# untitled1.net
KiCad netlist of a schematic drawn in EAGLE
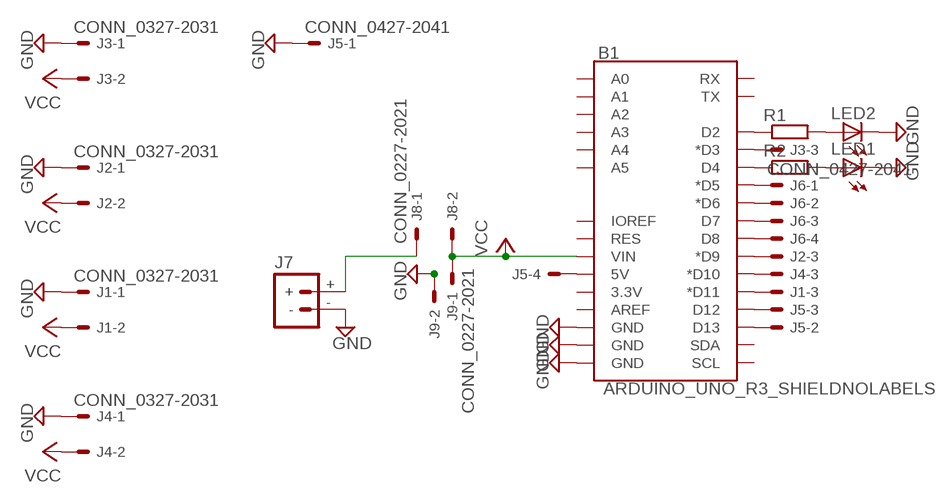
[diagram p0: schematic, sheet 1]

(export (version "E")
  (design (tool "Eeschema 10.0.6"))
  (components
    (comp (ref "B1")
      (value "ARDUINO_UNO_R3_SHIELDNOLABELS")
      (footprint "eagle-import:UNO_R3_SHIELD_NOLABELS")
      (libsource (lib "eagle-import") (part "ARDUINO_UNO_R3_SHIELDNOLABELS"))
    )
    (comp (ref "J1")
      (value "CONN_0327-2031")
      (footprint "eagle-import:6410-03")
      (libsource (lib "eagle-import") (part "CONN_0327-2031"))
    )
    (comp (ref "J2")
      (value "CONN_0327-2031")
      (footprint "eagle-import:6410-03")
      (libsource (lib "eagle-import") (part "CONN_0327-2031"))
    )
    (comp (ref "J3")
      (value "CONN_0327-2031")
      (footprint "eagle-import:6410-03")
      (libsource (lib "eagle-import") (part "CONN_0327-2031"))
    )
    (comp (ref "J4")
      (value "CONN_0327-2031")
      (footprint "eagle-import:6410-03")
      (libsource (lib "eagle-import") (part "CONN_0327-2031"))
    )
    (comp (ref "J5")
      (value "CONN_0427-2041")
      (footprint "eagle-import:6410-04")
      (libsource (lib "eagle-import") (part "CONN_0427-2041"))
    )
    (comp (ref "J6")
      (value "CONN_0427-2041")
      (footprint "eagle-import:6410-04")
      (libsource (lib "eagle-import") (part "CONN_0427-2041"))
    )
    (comp (ref "J7")
      (value "BATTERY_CONNXT60")
      (footprint "eagle-import:XT60")
      (libsource (lib "eagle-import") (part "BATTERY_CONNXT60"))
    )
    (comp (ref "J8")
      (value "CONN_0227-2021")
      (footprint "eagle-import:6410-02")
      (libsource (lib "eagle-import") (part "CONN_0227-2021"))
    )
    (comp (ref "J9")
      (value "CONN_0227-2021")
      (footprint "eagle-import:6410-02")
      (libsource (lib "eagle-import") (part "CONN_0227-2021"))
    )
    (comp (ref "LED1")
      (value "LED5MM")
      (footprint "eagle-import:LED5MM")
      (libsource (lib "eagle-import") (part "LED5MM"))
    )
    (comp (ref "LED2")
      (value "LED5MM")
      (footprint "eagle-import:LED5MM")
      (libsource (lib "eagle-import") (part "LED5MM"))
    )
    (comp (ref "R1")
      (value "R-EU_0204/7")
      (footprint "eagle-import:0204_7")
      (libsource (lib "eagle-import") (part "R-EU_0204/7"))
    )
    (comp (ref "R2")
      (value "R-EU_0204/7")
      (footprint "eagle-import:0204_7")
      (libsource (lib "eagle-import") (part "R-EU_0204/7"))
    )
  )
  (nets
    (net (code "1") (name "GND") (class "Default")
      (node (ref "B1") (pin "GND@0") (pinfunction "GND_GND@0") (pintype "bidirectional"))
      (node (ref "B1") (pin "GND@1") (pinfunction "GND_GND@1") (pintype "bidirectional"))
      (node (ref "B1") (pin "GND@2") (pinfunction "GND_GND@2") (pintype "bidirectional"))
      (node (ref "J1") (pin "1") (pinfunction "S_1") (pintype "passive"))
      (node (ref "J2") (pin "1") (pinfunction "S_1") (pintype "passive"))
      (node (ref "J3") (pin "1") (pinfunction "S_1") (pintype "passive"))
      (node (ref "J4") (pin "1") (pinfunction "S_1") (pintype "passive"))
      (node (ref "J5") (pin "1") (pinfunction "S_1") (pintype "passive"))
      (node (ref "J7") (pin "-") (pinfunction "-_-") (pintype "passive"))
      (node (ref "J9") (pin "2") (pinfunction "S_2") (pintype "passive"))
      (node (ref "LED1") (pin "K") (pinfunction "C_K") (pintype "passive"))
      (node (ref "LED2") (pin "K") (pinfunction "C_K") (pintype "passive"))
    )
    (net (code "2") (name "Net-(B1-*D3)") (class "Default")
      (node (ref "B1") (pin "D3") (pinfunction "*D3_D3") (pintype "bidirectional"))
      (node (ref "J3") (pin "3") (pinfunction "S_3") (pintype "passive"))
    )
    (net (code "3") (name "Net-(B1-*D5)") (class "Default")
      (node (ref "B1") (pin "D5") (pinfunction "*D5_D5") (pintype "bidirectional"))
      (node (ref "J6") (pin "1") (pinfunction "S_1") (pintype "passive"))
    )
    (net (code "4") (name "Net-(B1-*D6)") (class "Default")
      (node (ref "B1") (pin "D6") (pinfunction "*D6_D6") (pintype "bidirectional"))
      (node (ref "J6") (pin "2") (pinfunction "S_2") (pintype "passive"))
    )
    (net (code "5") (name "Net-(B1-*D9)") (class "Default")
      (node (ref "B1") (pin "D9") (pinfunction "*D9_D9") (pintype "bidirectional"))
      (node (ref "J2") (pin "3") (pinfunction "S_3") (pintype "passive"))
    )
    (net (code "6") (name "Net-(B1-*D10)") (class "Default")
      (node (ref "B1") (pin "D10") (pinfunction "*D10_D10") (pintype "bidirectional"))
      (node (ref "J4") (pin "3") (pinfunction "S_3") (pintype "passive"))
    )
    (net (code "7") (name "Net-(B1-*D11)") (class "Default")
      (node (ref "B1") (pin "D11") (pinfunction "*D11_D11") (pintype "bidirectional"))
      (node (ref "J1") (pin "3") (pinfunction "S_3") (pintype "passive"))
    )
    (net (code "8") (name "Net-(B1-PadD2)") (class "Default")
      (node (ref "B1") (pin "D2") (pinfunction "D2_D2") (pintype "bidirectional"))
      (node (ref "R1") (pin "1") (pinfunction "1_1") (pintype "passive"))
    )
    (net (code "9") (name "Net-(B1-PadD4)") (class "Default")
      (node (ref "B1") (pin "D4") (pinfunction "D4_D4") (pintype "bidirectional"))
      (node (ref "R2") (pin "1") (pinfunction "1_1") (pintype "passive"))
    )
    (net (code "10") (name "Net-(J5B-S)") (class "Default")
      (node (ref "B1") (pin "D13") (pinfunction "D13_D13") (pintype "bidirectional"))
      (node (ref "J5") (pin "2") (pinfunction "S_2") (pintype "passive"))
    )
    (net (code "11") (name "Net-(J5C-S)") (class "Default")
      (node (ref "B1") (pin "D12") (pinfunction "D12_D12") (pintype "bidirectional"))
      (node (ref "J5") (pin "3") (pinfunction "S_3") (pintype "passive"))
    )
    (net (code "12") (name "Net-(J5D-S)") (class "Default")
      (node (ref "B1") (pin "5V") (pinfunction "5V_5V") (pintype "bidirectional"))
      (node (ref "J5") (pin "4") (pinfunction "S_4") (pintype "passive"))
    )
    (net (code "13") (name "Net-(J6C-S)") (class "Default")
      (node (ref "B1") (pin "D7") (pinfunction "D7_D7") (pintype "bidirectional"))
      (node (ref "J6") (pin "3") (pinfunction "S_3") (pintype "passive"))
    )
    (net (code "14") (name "Net-(J6D-S)") (class "Default")
      (node (ref "B1") (pin "D8") (pinfunction "D8_D8") (pintype "bidirectional"))
      (node (ref "J6") (pin "4") (pinfunction "S_4") (pintype "passive"))
    )
    (net (code "15") (name "Net-(J8A-S)") (class "Default")
      (node (ref "J7") (pin "+") (pinfunction "+_+") (pintype "passive"))
      (node (ref "J8") (pin "1") (pinfunction "S_1") (pintype "passive"))
    )
    (net (code "16") (name "Net-(LED1-PadA)") (class "Default")
      (node (ref "LED1") (pin "A") (pinfunction "A_A") (pintype "passive"))
      (node (ref "R2") (pin "2") (pinfunction "2_2") (pintype "passive"))
    )
    (net (code "17") (name "Net-(LED2-PadA)") (class "Default")
      (node (ref "LED2") (pin "A") (pinfunction "A_A") (pintype "passive"))
      (node (ref "R1") (pin "2") (pinfunction "2_2") (pintype "passive"))
    )
    (net (code "18") (name "VCC") (class "Default")
      (node (ref "B1") (pin "VIN") (pinfunction "VIN_VIN") (pintype "bidirectional"))
      (node (ref "J1") (pin "2") (pinfunction "S_2") (pintype "passive"))
      (node (ref "J2") (pin "2") (pinfunction "S_2") (pintype "passive"))
      (node (ref "J3") (pin "2") (pinfunction "S_2") (pintype "passive"))
      (node (ref "J4") (pin "2") (pinfunction "S_2") (pintype "passive"))
      (node (ref "J8") (pin "2") (pinfunction "S_2") (pintype "passive"))
      (node (ref "J9") (pin "1") (pinfunction "S_1") (pintype "passive"))
    )
    (net (code "19") (name "unconnected-(B1-Pad3.3V)") (class "Default")
      (node (ref "B1") (pin "3.3V") (pinfunction "3.3V_3.3V") (pintype "bidirectional"))
    )
    (net (code "20") (name "unconnected-(B1-PadA0)") (class "Default")
      (node (ref "B1") (pin "A0") (pinfunction "A0_A0") (pintype "bidirectional"))
    )
    (net (code "21") (name "unconnected-(B1-PadA1)") (class "Default")
      (node (ref "B1") (pin "A1") (pinfunction "A1_A1") (pintype "bidirectional"))
    )
    (net (code "22") (name "unconnected-(B1-PadA2)") (class "Default")
      (node (ref "B1") (pin "A2") (pinfunction "A2_A2") (pintype "bidirectional"))
    )
    (net (code "23") (name "unconnected-(B1-PadA3)") (class "Default")
      (node (ref "B1") (pin "A3") (pinfunction "A3_A3") (pintype "bidirectional"))
    )
    (net (code "24") (name "unconnected-(B1-PadA4)") (class "Default")
      (node (ref "B1") (pin "A4") (pinfunction "A4_A4") (pintype "bidirectional"))
    )
    (net (code "25") (name "unconnected-(B1-PadA5)") (class "Default")
      (node (ref "B1") (pin "A5") (pinfunction "A5_A5") (pintype "bidirectional"))
    )
    (net (code "26") (name "unconnected-(B1-PadAREF)") (class "Default")
      (node (ref "B1") (pin "AREF") (pinfunction "AREF_AREF") (pintype "bidirectional"))
    )
    (net (code "27") (name "unconnected-(B1-PadIOREF)") (class "Default")
      (node (ref "B1") (pin "IOREF") (pinfunction "IOREF_IOREF") (pintype "bidirectional"))
    )
    (net (code "28") (name "unconnected-(B1-PadRES)") (class "Default")
      (node (ref "B1") (pin "RES") (pinfunction "RES_RES") (pintype "bidirectional"))
    )
    (net (code "29") (name "unconnected-(B1-PadRX)") (class "Default")
      (node (ref "B1") (pin "RX") (pinfunction "RX_RX") (pintype "bidirectional"))
    )
    (net (code "30") (name "unconnected-(B1-PadSCL)") (class "Default")
      (node (ref "B1") (pin "SCL") (pinfunction "SCL_SCL") (pintype "bidirectional"))
    )
    (net (code "31") (name "unconnected-(B1-PadSDA)") (class "Default")
      (node (ref "B1") (pin "SDA") (pinfunction "SDA_SDA") (pintype "bidirectional"))
    )
    (net (code "32") (name "unconnected-(B1-PadTX)") (class "Default")
      (node (ref "B1") (pin "TX") (pinfunction "TX_TX") (pintype "bidirectional"))
    )
  )
)
